# schematic_rovables_master_v1.net
KiCad netlist of a schematic drawn in Altium Designer
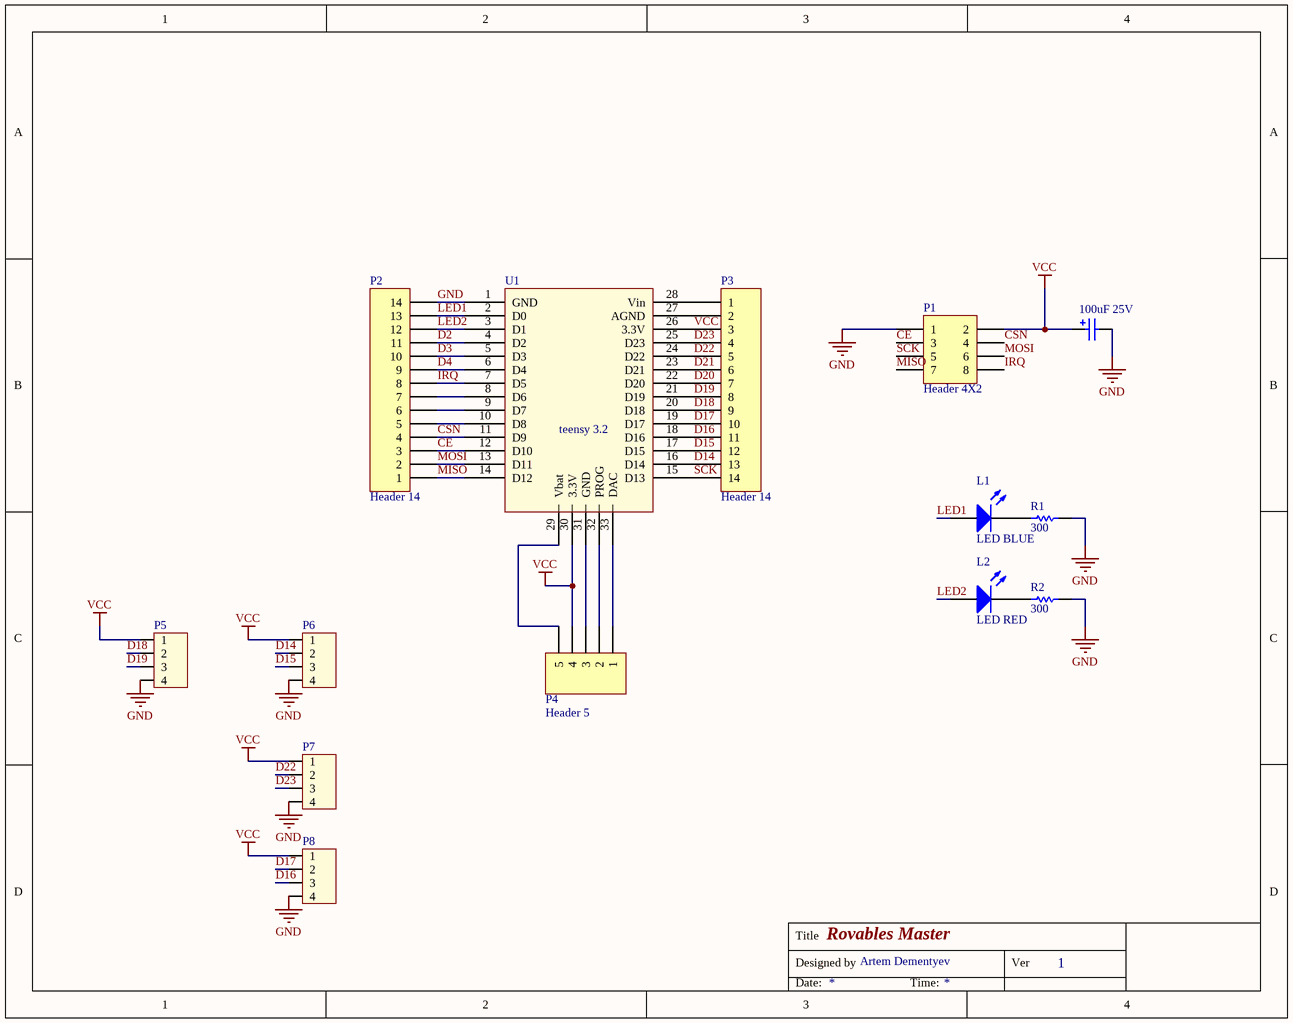
[diagram p0: schematic_rovables_master_v1.SchDoc]

(export (version "E")
  (design (tool "Eeschema 10.0.6"))
  (components
    (comp (ref "100uF 25V")
      (value "Electrolytic Cap 100uF smd")
      (footprint "F80 Electrolytic cap")
      (description "100uF 25 VSMD")
      (fields
        (field (name "DIGIKEY PART NUMBER") "565-2549-1-ND")
        (field (name "MANUFACTURER") "United Chemi-Con")
      )
      (libsource (lib "Artem_Library") (part "Electrolytic Cap 100uF smd"))
    )
    (comp (ref "L1")
      (value "LED BLUE")
      (footprint "RES_1206_SMD")
      (description "LED SMD 1206/0603")
      (libsource (lib "Artem_Library") (part "LED"))
    )
    (comp (ref "L2")
      (value "LED RED")
      (footprint "RES_1206_SMD")
      (description "LED SMD 1206/0603")
      (libsource (lib "Artem_Library") (part "LED"))
    )
    (comp (ref "P1")
      (value "Header 4X2")
      (footprint "HDR2X4")
      (description "Header, 4-Pin, Dual row")
      (fields (field (name "PUBLISHER") "Altium Limited"))
      (libsource (lib "Miscellaneous Connectors") (part "Header 4X2"))
    )
    (comp (ref "P2")
      (value "Header 14")
      (footprint "HDR1X14")
      (description "Header, 14-Pin")
      (fields (field (name "PUBLISHER") "Altium Limited"))
      (libsource (lib "Miscellaneous Connectors") (part "Header 14"))
    )
    (comp (ref "P3")
      (value "Header 14")
      (footprint "HDR1X14")
      (description "Header, 14-Pin")
      (fields (field (name "PUBLISHER") "Altium Limited"))
      (libsource (lib "") (part "Header 14_1"))
    )
    (comp (ref "P4")
      (value "Header 5")
      (footprint "HDR1X5")
      (description "Header, 5-Pin")
      (fields (field (name "PUBLISHER") "Altium Limited"))
      (libsource (lib "Miscellaneous Connectors") (part "Header 5"))
    )
    (comp (ref "P5")
      (value "JST SH 4 SIDE")
      (footprint "JST SH 4 TOP ENTRY")
      (fields
        (field (name "DIGIKEY PART NUMBER") "455-1804-1-ND")
        (field (name "MANUFACTURER PART NUMBER") "SM04B-SRSS-TB(LF)(SN)")
        (field (name "MANUFACTURER") "JST")
      )
      (libsource (lib "Artem_Library") (part "JST SH 4 SIDE"))
    )
    (comp (ref "P6")
      (value "JST SH 4 SIDE")
      (footprint "JST SH 4 TOP ENTRY")
      (fields
        (field (name "DIGIKEY PART NUMBER") "455-1804-1-ND")
        (field (name "MANUFACTURER PART NUMBER") "SM04B-SRSS-TB(LF)(SN)")
        (field (name "MANUFACTURER") "JST")
      )
      (libsource (lib "Artem_Library") (part "JST SH 4 SIDE"))
    )
    (comp (ref "P7")
      (value "JST SH 4 SIDE")
      (footprint "JST SH 4 TOP ENTRY")
      (fields
        (field (name "DIGIKEY PART NUMBER") "455-1804-1-ND")
        (field (name "MANUFACTURER PART NUMBER") "SM04B-SRSS-TB(LF)(SN)")
        (field (name "MANUFACTURER") "JST")
      )
      (libsource (lib "Artem_Library") (part "JST SH 4 SIDE"))
    )
    (comp (ref "P8")
      (value "JST SH 4 SIDE")
      (footprint "JST SH 4 TOP ENTRY")
      (fields
        (field (name "DIGIKEY PART NUMBER") "455-1804-1-ND")
        (field (name "MANUFACTURER PART NUMBER") "SM04B-SRSS-TB(LF)(SN)")
        (field (name "MANUFACTURER") "JST")
      )
      (libsource (lib "Artem_Library") (part "JST SH 4 SIDE"))
    )
    (comp (ref "R1")
      (value "300")
      (footprint "RES_1206_SMD")
      (libsource (lib "Artem_Library") (part "Resistor"))
    )
    (comp (ref "R2")
      (value "300")
      (footprint "RES_1206_SMD")
      (libsource (lib "Artem_Library") (part "Resistor"))
    )
    (comp (ref "U1")
      (value "teensy 3.2")
      (footprint "Teensy 3.2")
      (libsource (lib "Artem_Library") (part "teensy 3.2"))
    )
  )
  (nets
    (net (code "1") (name "/CE") (class "Default")
      (node (ref "P1") (pin "3") (pinfunction "3_3") (pintype "passive"))
      (node (ref "P2") (pin "3") (pinfunction "3_3") (pintype "passive"))
      (node (ref "U1") (pin "12") (pinfunction "D10_12") (pintype "passive"))
    )
    (net (code "2") (name "/CSN") (class "Default")
      (node (ref "P1") (pin "4") (pinfunction "4_4") (pintype "passive"))
      (node (ref "P2") (pin "4") (pinfunction "4_4") (pintype "passive"))
      (node (ref "U1") (pin "11") (pinfunction "D9_11") (pintype "passive"))
    )
    (net (code "3") (name "/D2") (class "Default")
      (node (ref "P2") (pin "11") (pinfunction "11_11") (pintype "passive"))
      (node (ref "U1") (pin "4") (pinfunction "D2_4") (pintype "passive"))
    )
    (net (code "4") (name "/D3") (class "Default")
      (node (ref "P2") (pin "10") (pinfunction "10_10") (pintype "passive"))
      (node (ref "U1") (pin "5") (pinfunction "D3_5") (pintype "passive"))
    )
    (net (code "5") (name "/D4") (class "Default")
      (node (ref "P2") (pin "9") (pinfunction "9_9") (pintype "passive"))
      (node (ref "U1") (pin "6") (pinfunction "D4_6") (pintype "passive"))
    )
    (net (code "6") (name "/D14") (class "Default")
      (node (ref "P3") (pin "13") (pinfunction "13_13") (pintype "passive"))
      (node (ref "P6") (pin "2") (pinfunction "2_2") (pintype "passive"))
      (node (ref "U1") (pin "16") (pinfunction "D14_16") (pintype "passive"))
    )
    (net (code "7") (name "/D15") (class "Default")
      (node (ref "P3") (pin "12") (pinfunction "12_12") (pintype "passive"))
      (node (ref "P6") (pin "3") (pinfunction "3_3") (pintype "passive"))
      (node (ref "U1") (pin "17") (pinfunction "D15_17") (pintype "passive"))
    )
    (net (code "8") (name "/D16") (class "Default")
      (node (ref "P3") (pin "11") (pinfunction "11_11") (pintype "passive"))
      (node (ref "P8") (pin "3") (pinfunction "3_3") (pintype "passive"))
      (node (ref "U1") (pin "18") (pinfunction "D16_18") (pintype "passive"))
    )
    (net (code "9") (name "/D17") (class "Default")
      (node (ref "P3") (pin "10") (pinfunction "10_10") (pintype "passive"))
      (node (ref "P8") (pin "2") (pinfunction "2_2") (pintype "passive"))
      (node (ref "U1") (pin "19") (pinfunction "D17_19") (pintype "passive"))
    )
    (net (code "10") (name "/D18") (class "Default")
      (node (ref "P3") (pin "9") (pinfunction "9_9") (pintype "passive"))
      (node (ref "P5") (pin "2") (pinfunction "2_2") (pintype "passive"))
      (node (ref "U1") (pin "20") (pinfunction "D18_20") (pintype "passive"))
    )
    (net (code "11") (name "/D19") (class "Default")
      (node (ref "P3") (pin "8") (pinfunction "8_8") (pintype "passive"))
      (node (ref "P5") (pin "3") (pinfunction "3_3") (pintype "passive"))
      (node (ref "U1") (pin "21") (pinfunction "D19_21") (pintype "passive"))
    )
    (net (code "12") (name "/D20") (class "Default")
      (node (ref "P3") (pin "7") (pinfunction "7_7") (pintype "passive"))
      (node (ref "U1") (pin "22") (pinfunction "D20_22") (pintype "passive"))
    )
    (net (code "13") (name "/D21") (class "Default")
      (node (ref "P3") (pin "6") (pinfunction "6_6") (pintype "passive"))
      (node (ref "U1") (pin "23") (pinfunction "D21_23") (pintype "passive"))
    )
    (net (code "14") (name "/D22") (class "Default")
      (node (ref "P3") (pin "5") (pinfunction "5_5") (pintype "passive"))
      (node (ref "P7") (pin "2") (pinfunction "2_2") (pintype "passive"))
      (node (ref "U1") (pin "24") (pinfunction "D22_24") (pintype "passive"))
    )
    (net (code "15") (name "/D23") (class "Default")
      (node (ref "P3") (pin "4") (pinfunction "4_4") (pintype "passive"))
      (node (ref "P7") (pin "3") (pinfunction "3_3") (pintype "passive"))
      (node (ref "U1") (pin "25") (pinfunction "D23_25") (pintype "passive"))
    )
    (net (code "16") (name "/IRQ") (class "Default")
      (node (ref "P1") (pin "8") (pinfunction "8_8") (pintype "passive"))
      (node (ref "P2") (pin "8") (pinfunction "8_8") (pintype "passive"))
      (node (ref "U1") (pin "7") (pinfunction "D5_7") (pintype "passive"))
    )
    (net (code "17") (name "/LED1") (class "Default")
      (node (ref "L1") (pin "1") (pinfunction "A_1") (pintype "passive"))
      (node (ref "P2") (pin "13") (pinfunction "13_13") (pintype "passive"))
      (node (ref "U1") (pin "2") (pinfunction "D0_2") (pintype "passive"))
    )
    (net (code "18") (name "/LED2") (class "Default")
      (node (ref "L2") (pin "1") (pinfunction "A_1") (pintype "passive"))
      (node (ref "P2") (pin "12") (pinfunction "12_12") (pintype "passive"))
      (node (ref "U1") (pin "3") (pinfunction "D1_3") (pintype "passive"))
    )
    (net (code "19") (name "/MISO") (class "Default")
      (node (ref "P1") (pin "7") (pinfunction "7_7") (pintype "passive"))
      (node (ref "P2") (pin "1") (pinfunction "1_1") (pintype "passive"))
      (node (ref "U1") (pin "14") (pinfunction "D12_14") (pintype "passive"))
    )
    (net (code "20") (name "/MOSI") (class "Default")
      (node (ref "P1") (pin "6") (pinfunction "6_6") (pintype "passive"))
      (node (ref "P2") (pin "2") (pinfunction "2_2") (pintype "passive"))
      (node (ref "U1") (pin "13") (pinfunction "D11_13") (pintype "passive"))
    )
    (net (code "21") (name "/SCK") (class "Default")
      (node (ref "P1") (pin "5") (pinfunction "5_5") (pintype "passive"))
      (node (ref "P3") (pin "14") (pinfunction "14_14") (pintype "passive"))
      (node (ref "U1") (pin "15") (pinfunction "D13_15") (pintype "passive"))
    )
    (net (code "22") (name "GND") (class "Default")
      (node (ref "100uF 25V") (pin "2") (pinfunction "2_2") (pintype "passive"))
      (node (ref "P1") (pin "1") (pinfunction "1_1") (pintype "passive"))
      (node (ref "P2") (pin "14") (pinfunction "14_14") (pintype "passive"))
      (node (ref "P5") (pin "4") (pinfunction "4_4") (pintype "passive"))
      (node (ref "P6") (pin "4") (pinfunction "4_4") (pintype "passive"))
      (node (ref "P7") (pin "4") (pinfunction "4_4") (pintype "passive"))
      (node (ref "P8") (pin "4") (pinfunction "4_4") (pintype "passive"))
      (node (ref "R1") (pin "2") (pinfunction "2_2") (pintype "passive"))
      (node (ref "R2") (pin "2") (pinfunction "2_2") (pintype "passive"))
      (node (ref "U1") (pin "1") (pinfunction "GND_1") (pintype "passive"))
    )
    (net (code "23") (name "Net-(L1-K)") (class "Default")
      (node (ref "L1") (pin "2") (pinfunction "K_2") (pintype "passive"))
      (node (ref "R1") (pin "1") (pinfunction "1_1") (pintype "passive"))
    )
    (net (code "24") (name "Net-(L2-K)") (class "Default")
      (node (ref "L2") (pin "2") (pinfunction "K_2") (pintype "passive"))
      (node (ref "R2") (pin "1") (pinfunction "1_1") (pintype "passive"))
    )
    (net (code "25") (name "Net-(P4-Pad3)") (class "Default")
      (node (ref "P4") (pin "3") (pinfunction "3_3") (pintype "passive"))
      (node (ref "U1") (pin "31") (pinfunction "GND_31") (pintype "passive"))
    )
    (net (code "26") (name "Net-(U1-AGND)") (class "Default")
      (node (ref "P3") (pin "2") (pinfunction "2_2") (pintype "passive"))
      (node (ref "U1") (pin "27") (pinfunction "AGND_27") (pintype "passive"))
    )
    (net (code "27") (name "Net-(U1-D6)") (class "Default")
      (node (ref "P2") (pin "7") (pinfunction "7_7") (pintype "passive"))
      (node (ref "U1") (pin "8") (pinfunction "D6_8") (pintype "passive"))
    )
    (net (code "28") (name "Net-(U1-D7)") (class "Default")
      (node (ref "P2") (pin "6") (pinfunction "6_6") (pintype "passive"))
      (node (ref "U1") (pin "9") (pinfunction "D7_9") (pintype "passive"))
    )
    (net (code "29") (name "Net-(U1-D8)") (class "Default")
      (node (ref "P2") (pin "5") (pinfunction "5_5") (pintype "passive"))
      (node (ref "U1") (pin "10") (pinfunction "D8_10") (pintype "passive"))
    )
    (net (code "30") (name "Net-(U1-DAC)") (class "Default")
      (node (ref "P4") (pin "1") (pinfunction "1_1") (pintype "passive"))
      (node (ref "U1") (pin "33") (pinfunction "DAC_33") (pintype "passive"))
    )
    (net (code "31") (name "Net-(U1-PROG)") (class "Default")
      (node (ref "P4") (pin "2") (pinfunction "2_2") (pintype "passive"))
      (node (ref "U1") (pin "32") (pinfunction "PROG_32") (pintype "passive"))
    )
    (net (code "32") (name "Net-(U1-Vbat)") (class "Default")
      (node (ref "P4") (pin "5") (pinfunction "5_5") (pintype "passive"))
      (node (ref "U1") (pin "29") (pinfunction "Vbat_29") (pintype "passive"))
    )
    (net (code "33") (name "Net-(U1-Vin)") (class "Default")
      (node (ref "P3") (pin "1") (pinfunction "1_1") (pintype "passive"))
      (node (ref "U1") (pin "28") (pinfunction "Vin_28") (pintype "passive"))
    )
    (net (code "34") (name "VCC") (class "Default")
      (node (ref "100uF 25V") (pin "1") (pinfunction "1_1") (pintype "passive"))
      (node (ref "P1") (pin "2") (pinfunction "2_2") (pintype "passive"))
      (node (ref "P3") (pin "3") (pinfunction "3_3") (pintype "passive"))
      (node (ref "P4") (pin "4") (pinfunction "4_4") (pintype "passive"))
      (node (ref "P5") (pin "1") (pinfunction "1_1") (pintype "passive"))
      (node (ref "P6") (pin "1") (pinfunction "1_1") (pintype "passive"))
      (node (ref "P7") (pin "1") (pinfunction "1_1") (pintype "passive"))
      (node (ref "P8") (pin "1") (pinfunction "1_1") (pintype "passive"))
      (node (ref "U1") (pin "26") (pinfunction "3.3V_26") (pintype "passive"))
      (node (ref "U1") (pin "30") (pinfunction "3.3V_30") (pintype "passive"))
    )
  )
)
